# WAVESeeed.net
KiCad netlist of a schematic drawn in EAGLE
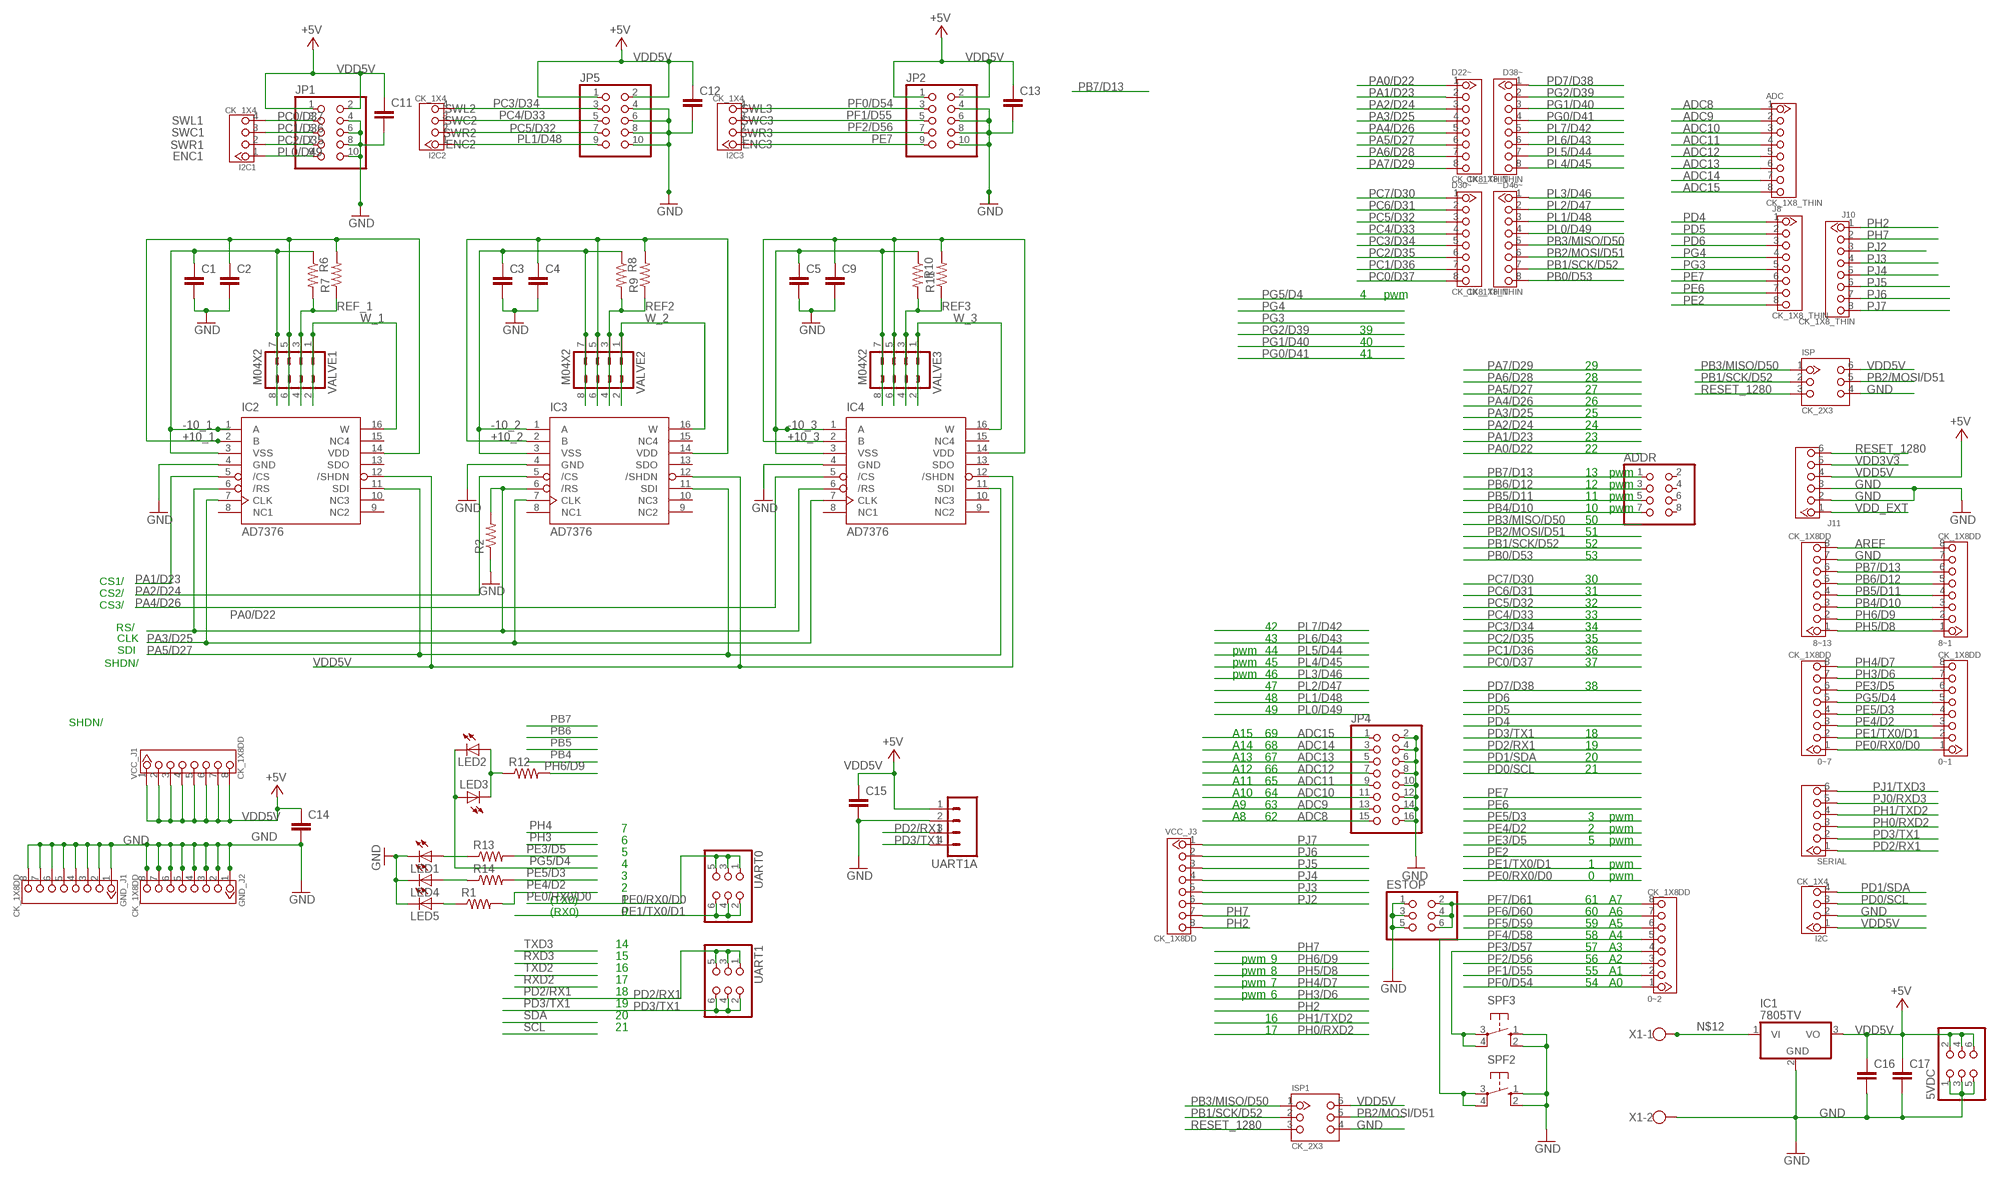
[diagram p0: schematic, sheet 1]

(export (version "E")
  (design (tool "Eeschema 10.0.6"))
  (components
    (comp (ref "0~1")
      (value "CK_1X8DD")
      (footprint "eagle-import:CK_1X8")
      (libsource (lib "eagle-import") (part "CK_1X8DD"))
    )
    (comp (ref "0~2")
      (value "CK_1X8DD")
      (footprint "eagle-import:CK_1X8")
      (libsource (lib "eagle-import") (part "CK_1X8DD"))
    )
    (comp (ref "0~7")
      (value "CK_1X8DD")
      (footprint "eagle-import:CK_1X8")
      (libsource (lib "eagle-import") (part "CK_1X8DD"))
    )
    (comp (ref "5VDC")
      (value "PINHD-2X3")
      (footprint "eagle-import:2X03")
      (libsource (lib "eagle-import") (part "PINHD-2X3"))
    )
    (comp (ref "8~1")
      (value "CK_1X8DD")
      (footprint "eagle-import:CK_1X8")
      (libsource (lib "eagle-import") (part "CK_1X8DD"))
    )
    (comp (ref "8~13")
      (value "CK_1X8DD")
      (footprint "eagle-import:CK_1X8")
      (libsource (lib "eagle-import") (part "CK_1X8DD"))
    )
    (comp (ref "ADC")
      (value "CK_1X8_THIN")
      (footprint "eagle-import:CK_1X8_THIN")
      (libsource (lib "eagle-import") (part "CK_1X8_THIN"))
    )
    (comp (ref "ADDR")
      (value "PINHD-2X4")
      (footprint "eagle-import:2X04")
      (libsource (lib "eagle-import") (part "PINHD-2X4"))
    )
    (comp (ref "C1")
      (value "C-EUC1206")
      (footprint "eagle-import:C1206")
      (libsource (lib "eagle-import") (part "C-EUC1206"))
    )
    (comp (ref "C2")
      (value "C-EUC1206")
      (footprint "eagle-import:C1206")
      (libsource (lib "eagle-import") (part "C-EUC1206"))
    )
    (comp (ref "C3")
      (value "C-EUC1206")
      (footprint "eagle-import:C1206")
      (libsource (lib "eagle-import") (part "C-EUC1206"))
    )
    (comp (ref "C4")
      (value "C-EUC1206")
      (footprint "eagle-import:C1206")
      (libsource (lib "eagle-import") (part "C-EUC1206"))
    )
    (comp (ref "C5")
      (value "C-EUC1206")
      (footprint "eagle-import:C1206")
      (libsource (lib "eagle-import") (part "C-EUC1206"))
    )
    (comp (ref "C9")
      (value "C-EUC1206")
      (footprint "eagle-import:C1206")
      (libsource (lib "eagle-import") (part "C-EUC1206"))
    )
    (comp (ref "C11")
      (value "C-EUC1206")
      (footprint "eagle-import:C1206")
      (libsource (lib "eagle-import") (part "C-EUC1206"))
    )
    (comp (ref "C12")
      (value "C-EUC1206K")
      (footprint "eagle-import:C1206K")
      (libsource (lib "eagle-import") (part "C-EUC1206K"))
    )
    (comp (ref "C13")
      (value "C-EUC1206K")
      (footprint "eagle-import:C1206K")
      (libsource (lib "eagle-import") (part "C-EUC1206K"))
    )
    (comp (ref "C14")
      (value "C-EUC1206K")
      (footprint "eagle-import:C1206K")
      (libsource (lib "eagle-import") (part "C-EUC1206K"))
    )
    (comp (ref "C15")
      (value "C-EUC1206")
      (footprint "eagle-import:C1206")
      (libsource (lib "eagle-import") (part "C-EUC1206"))
    )
    (comp (ref "C16")
      (value "C-EUC1206")
      (footprint "eagle-import:C1206")
      (libsource (lib "eagle-import") (part "C-EUC1206"))
    )
    (comp (ref "C17")
      (value "C-EUC1206K")
      (footprint "eagle-import:C1206K")
      (libsource (lib "eagle-import") (part "C-EUC1206K"))
    )
    (comp (ref "D22~")
      (value "CK_1X8_THIN")
      (footprint "eagle-import:CK_1X8_THIN")
      (libsource (lib "eagle-import") (part "CK_1X8_THIN"))
    )
    (comp (ref "D30~")
      (value "CK_1X8_THIN")
      (footprint "eagle-import:CK_1X8_THIN")
      (libsource (lib "eagle-import") (part "CK_1X8_THIN"))
    )
    (comp (ref "D38~")
      (value "CK_1X8_THIN")
      (footprint "eagle-import:CK_1X8_THIN")
      (libsource (lib "eagle-import") (part "CK_1X8_THIN"))
    )
    (comp (ref "D46~")
      (value "CK_1X8_THIN")
      (footprint "eagle-import:CK_1X8_THIN")
      (libsource (lib "eagle-import") (part "CK_1X8_THIN"))
    )
    (comp (ref "ESTOP")
      (value "PINHD-2X3")
      (footprint "eagle-import:2X03")
      (libsource (lib "eagle-import") (part "PINHD-2X3"))
    )
    (comp (ref "GND_J1")
      (value "CK_1X8DD")
      (footprint "eagle-import:CK_1X8")
      (libsource (lib "eagle-import") (part "CK_1X8DD"))
    )
    (comp (ref "GND_J2")
      (value "CK_1X8DD")
      (footprint "eagle-import:CK_1X8")
      (libsource (lib "eagle-import") (part "CK_1X8DD"))
    )
    (comp (ref "I2C")
      (value "CK_1X4")
      (footprint "eagle-import:CK_1X4")
      (libsource (lib "eagle-import") (part "CK_1X4_DD"))
    )
    (comp (ref "I2C1")
      (value "CK_1X4")
      (footprint "eagle-import:CK_1X4")
      (libsource (lib "eagle-import") (part "CK_1X4_DD"))
    )
    (comp (ref "I2C2")
      (value "CK_1X4")
      (footprint "eagle-import:CK_1X4")
      (libsource (lib "eagle-import") (part "CK_1X4_DD"))
    )
    (comp (ref "I2C3")
      (value "CK_1X4")
      (footprint "eagle-import:CK_1X4")
      (libsource (lib "eagle-import") (part "CK_1X4_DD"))
    )
    (comp (ref "IC1")
      (value "7805TV")
      (footprint "eagle-import:TO220V")
      (libsource (lib "eagle-import") (part "78TV05"))
    )
    (comp (ref "IC2")
      (value "AD7376")
      (footprint "eagle-import:SO-16W")
      (libsource (lib "eagle-import") (part "AD7376"))
    )
    (comp (ref "IC3")
      (value "AD7376")
      (footprint "eagle-import:SO-16W")
      (libsource (lib "eagle-import") (part "AD7376"))
    )
    (comp (ref "IC4")
      (value "AD7376")
      (footprint "eagle-import:SO-16W")
      (libsource (lib "eagle-import") (part "AD7376"))
    )
    (comp (ref "ISP")
      (value "CK_2X3")
      (footprint "eagle-import:CK_2X3_THIN")
      (libsource (lib "eagle-import") (part "CK_2X3_THIN"))
    )
    (comp (ref "ISP1")
      (value "CK_2X3")
      (footprint "eagle-import:CK_2X3_THIN")
      (libsource (lib "eagle-import") (part "CK_2X3_THIN"))
    )
    (comp (ref "J8")
      (value "CK_1X8_THIN")
      (footprint "eagle-import:CK_1X8_THIN")
      (libsource (lib "eagle-import") (part "CK_1X8_THIN"))
    )
    (comp (ref "J10")
      (value "CK_1X8_THIN")
      (footprint "eagle-import:CK_1X8_THIN")
      (libsource (lib "eagle-import") (part "CK_1X8_THIN"))
    )
    (comp (ref "J11")
      (value "CK_1X6")
      (footprint "eagle-import:CK_1X6")
      (libsource (lib "eagle-import") (part "CK_1X6"))
    )
    (comp (ref "JP1")
      (value "PINHD-2X5")
      (footprint "eagle-import:2X05")
      (libsource (lib "eagle-import") (part "PINHD-2X5"))
    )
    (comp (ref "JP2")
      (value "PINHD-2X5")
      (footprint "eagle-import:2X05")
      (libsource (lib "eagle-import") (part "PINHD-2X5"))
    )
    (comp (ref "JP4")
      (value "PINHD-2X8")
      (footprint "eagle-import:2X08")
      (libsource (lib "eagle-import") (part "PINHD-2X8"))
    )
    (comp (ref "JP5")
      (value "PINHD-2X5")
      (footprint "eagle-import:2X05")
      (libsource (lib "eagle-import") (part "PINHD-2X5"))
    )
    (comp (ref "LED1")
      (value "LEDCHIPLED_1206")
      (footprint "eagle-import:CHIPLED_1206")
      (libsource (lib "eagle-import") (part "LEDCHIPLED_1206"))
    )
    (comp (ref "LED2")
      (value "LEDCHIPLED_1206")
      (footprint "eagle-import:CHIPLED_1206")
      (libsource (lib "eagle-import") (part "LEDCHIPLED_1206"))
    )
    (comp (ref "LED3")
      (value "LEDCHIPLED_1206")
      (footprint "eagle-import:CHIPLED_1206")
      (libsource (lib "eagle-import") (part "LEDCHIPLED_1206"))
    )
    (comp (ref "LED4")
      (value "LEDCHIPLED_1206")
      (footprint "eagle-import:CHIPLED_1206")
      (libsource (lib "eagle-import") (part "LEDCHIPLED_1206"))
    )
    (comp (ref "LED5")
      (value "LEDCHIPLED_1206")
      (footprint "eagle-import:CHIPLED_1206")
      (libsource (lib "eagle-import") (part "LEDCHIPLED_1206"))
    )
    (comp (ref "R1")
      (value "R-US_R1206")
      (footprint "eagle-import:R1206")
      (libsource (lib "eagle-import") (part "R-US_R1206"))
    )
    (comp (ref "R2")
      (value "R-US_R1206")
      (footprint "eagle-import:R1206")
      (libsource (lib "eagle-import") (part "R-US_R1206"))
    )
    (comp (ref "R6")
      (value "R-US_M1206")
      (footprint "eagle-import:M1206")
      (libsource (lib "eagle-import") (part "R-US_M1206"))
    )
    (comp (ref "R7")
      (value "R-US_M1206")
      (footprint "eagle-import:M1206")
      (libsource (lib "eagle-import") (part "R-US_M1206"))
    )
    (comp (ref "R8")
      (value "R-US_M1206")
      (footprint "eagle-import:M1206")
      (libsource (lib "eagle-import") (part "R-US_M1206"))
    )
    (comp (ref "R9")
      (value "R-US_M1206")
      (footprint "eagle-import:M1206")
      (libsource (lib "eagle-import") (part "R-US_M1206"))
    )
    (comp (ref "R10")
      (value "R-US_M1206")
      (footprint "eagle-import:M1206")
      (libsource (lib "eagle-import") (part "R-US_M1206"))
    )
    (comp (ref "R11")
      (value "R-US_M1206")
      (footprint "eagle-import:M1206")
      (libsource (lib "eagle-import") (part "R-US_M1206"))
    )
    (comp (ref "R12")
      (value "R-US_R1206")
      (footprint "eagle-import:R1206")
      (libsource (lib "eagle-import") (part "R-US_R1206"))
    )
    (comp (ref "R13")
      (value "R-US_R1206")
      (footprint "eagle-import:R1206")
      (libsource (lib "eagle-import") (part "R-US_R1206"))
    )
    (comp (ref "R14")
      (value "R-US_R1206")
      (footprint "eagle-import:R1206")
      (libsource (lib "eagle-import") (part "R-US_R1206"))
    )
    (comp (ref "SERIAL")
      (value "CK_1X6")
      (footprint "eagle-import:CK_1X6")
      (libsource (lib "eagle-import") (part "CK_1X6"))
    )
    (comp (ref "SPF2")
      (value "10-XX")
      (footprint "eagle-import:B3F-10XX")
      (fields (field (name "MPN") "B3F-1000"))
      (libsource (lib "eagle-import") (part "10-XX"))
    )
    (comp (ref "SPF3")
      (value "10-XX")
      (footprint "eagle-import:B3F-10XX")
      (fields (field (name "MPN") "B3F-1000"))
      (libsource (lib "eagle-import") (part "10-XX"))
    )
    (comp (ref "UART0")
      (value "PINHD-2X3")
      (footprint "eagle-import:2X03")
      (libsource (lib "eagle-import") (part "PINHD-2X3"))
    )
    (comp (ref "UART1")
      (value "PINHD-2X3")
      (footprint "eagle-import:2X03")
      (libsource (lib "eagle-import") (part "PINHD-2X3"))
    )
    (comp (ref "UART1A")
      (value "M04PTH")
      (footprint "eagle-import:1X04")
      (libsource (lib "eagle-import") (part "M04PTH"))
    )
    (comp (ref "VALVE1")
      (value "M04X2")
      (footprint "eagle-import:2X4")
      (libsource (lib "eagle-import") (part "M04X2"))
    )
    (comp (ref "VALVE2")
      (value "M04X2")
      (footprint "eagle-import:2X4")
      (libsource (lib "eagle-import") (part "M04X2"))
    )
    (comp (ref "VALVE3")
      (value "M04X2")
      (footprint "eagle-import:2X4")
      (libsource (lib "eagle-import") (part "M04X2"))
    )
    (comp (ref "VCC_J1")
      (value "CK_1X8DD")
      (footprint "eagle-import:CK_1X8")
      (libsource (lib "eagle-import") (part "CK_1X8DD"))
    )
    (comp (ref "VCC_J3")
      (value "CK_1X8DD")
      (footprint "eagle-import:CK_1X8")
      (libsource (lib "eagle-import") (part "CK_1X8DD"))
    )
    (comp (ref "X1")
      (value "W237-102")
      (footprint "eagle-import:W237-102")
      (fields (field (name "MPN") "237-102"))
      (libsource (lib "eagle-import") (part "W237-102"))
    )
  )
  (nets
    (net (code "1") (name "+5V") (class "Default")
      (node (ref "5VDC") (pin "2") (pinfunction "2_2") (pintype "passive"))
      (node (ref "5VDC") (pin "4") (pinfunction "4_4") (pintype "passive"))
      (node (ref "5VDC") (pin "6") (pinfunction "6_6") (pintype "passive"))
      (node (ref "C11") (pin "1") (pinfunction "1_1") (pintype "passive"))
      (node (ref "C12") (pin "1") (pinfunction "1_1") (pintype "passive"))
      (node (ref "C13") (pin "1") (pinfunction "1_1") (pintype "passive"))
      (node (ref "C14") (pin "1") (pinfunction "1_1") (pintype "passive"))
      (node (ref "C15") (pin "1") (pinfunction "1_1") (pintype "passive"))
      (node (ref "C16") (pin "1") (pinfunction "1_1") (pintype "passive"))
      (node (ref "C17") (pin "1") (pinfunction "1_1") (pintype "passive"))
      (node (ref "I2C") (pin "1") (pinfunction "P$1_1") (pintype "bidirectional"))
      (node (ref "IC1") (pin "3") (pinfunction "VO_3") (pintype "passive"))
      (node (ref "IC2") (pin "12") (pinfunction "/SHDN_12") (pintype "input"))
      (node (ref "IC3") (pin "12") (pinfunction "/SHDN_12") (pintype "input"))
      (node (ref "IC4") (pin "12") (pinfunction "/SHDN_12") (pintype "input"))
      (node (ref "ISP") (pin "6") (pinfunction "P$6_6") (pintype "bidirectional"))
      (node (ref "ISP1") (pin "6") (pinfunction "P$6_6") (pintype "bidirectional"))
      (node (ref "J11") (pin "4") (pinfunction "4_4") (pintype "bidirectional"))
      (node (ref "JP1") (pin "1") (pinfunction "1_1") (pintype "passive"))
      (node (ref "JP1") (pin "2") (pinfunction "2_2") (pintype "passive"))
      (node (ref "JP2") (pin "1") (pinfunction "1_1") (pintype "passive"))
      (node (ref "JP2") (pin "2") (pinfunction "2_2") (pintype "passive"))
      (node (ref "JP5") (pin "1") (pinfunction "1_1") (pintype "passive"))
      (node (ref "JP5") (pin "2") (pinfunction "2_2") (pintype "passive"))
      (node (ref "UART1A") (pin "1") (pinfunction "1_1") (pintype "passive"))
      (node (ref "VCC_J1") (pin "1") (pinfunction "P$1_1") (pintype "bidirectional"))
      (node (ref "VCC_J1") (pin "2") (pinfunction "P$2_2") (pintype "bidirectional"))
      (node (ref "VCC_J1") (pin "3") (pinfunction "P$3_3") (pintype "bidirectional"))
      (node (ref "VCC_J1") (pin "4") (pinfunction "P$4_4") (pintype "bidirectional"))
      (node (ref "VCC_J1") (pin "5") (pinfunction "P$5_5") (pintype "bidirectional"))
      (node (ref "VCC_J1") (pin "6") (pinfunction "P$6_6") (pintype "bidirectional"))
      (node (ref "VCC_J1") (pin "7") (pinfunction "P$7_7") (pintype "bidirectional"))
      (node (ref "VCC_J1") (pin "8") (pinfunction "P$8_8") (pintype "bidirectional"))
    )
    (net (code "2") (name "/+10_1") (class "Default")
      (node (ref "C2") (pin "1") (pinfunction "1_1") (pintype "passive"))
      (node (ref "IC2") (pin "14") (pinfunction "VDD_14") (pintype "power_in"))
      (node (ref "IC2") (pin "2") (pinfunction "B_2") (pintype "bidirectional"))
      (node (ref "R7") (pin "2") (pinfunction "2_2") (pintype "passive"))
      (node (ref "VALVE1") (pin "5") (pinfunction "5_5") (pintype "passive"))
      (node (ref "VALVE1") (pin "6") (pinfunction "6_6") (pintype "passive"))
    )
    (net (code "3") (name "/+10_2") (class "Default")
      (node (ref "C4") (pin "1") (pinfunction "1_1") (pintype "passive"))
      (node (ref "IC3") (pin "14") (pinfunction "VDD_14") (pintype "power_in"))
      (node (ref "IC3") (pin "2") (pinfunction "B_2") (pintype "bidirectional"))
      (node (ref "R9") (pin "2") (pinfunction "2_2") (pintype "passive"))
      (node (ref "VALVE2") (pin "5") (pinfunction "5_5") (pintype "passive"))
      (node (ref "VALVE2") (pin "6") (pinfunction "6_6") (pintype "passive"))
    )
    (net (code "4") (name "/+10_3") (class "Default")
      (node (ref "C9") (pin "1") (pinfunction "1_1") (pintype "passive"))
      (node (ref "IC4") (pin "14") (pinfunction "VDD_14") (pintype "power_in"))
      (node (ref "IC4") (pin "2") (pinfunction "B_2") (pintype "bidirectional"))
      (node (ref "R11") (pin "2") (pinfunction "2_2") (pintype "passive"))
      (node (ref "VALVE3") (pin "5") (pinfunction "5_5") (pintype "passive"))
      (node (ref "VALVE3") (pin "6") (pinfunction "6_6") (pintype "passive"))
    )
    (net (code "5") (name "/-10_1") (class "Default")
      (node (ref "C1") (pin "1") (pinfunction "1_1") (pintype "passive"))
      (node (ref "IC2") (pin "1") (pinfunction "A_1") (pintype "bidirectional"))
      (node (ref "IC2") (pin "3") (pinfunction "VSS_3") (pintype "power_in"))
      (node (ref "R6") (pin "1") (pinfunction "1_1") (pintype "passive"))
      (node (ref "VALVE1") (pin "7") (pinfunction "7_7") (pintype "passive"))
      (node (ref "VALVE1") (pin "8") (pinfunction "8_8") (pintype "passive"))
    )
    (net (code "6") (name "/-10_2") (class "Default")
      (node (ref "C3") (pin "1") (pinfunction "1_1") (pintype "passive"))
      (node (ref "IC3") (pin "1") (pinfunction "A_1") (pintype "bidirectional"))
      (node (ref "IC3") (pin "3") (pinfunction "VSS_3") (pintype "power_in"))
      (node (ref "R8") (pin "1") (pinfunction "1_1") (pintype "passive"))
      (node (ref "VALVE2") (pin "7") (pinfunction "7_7") (pintype "passive"))
      (node (ref "VALVE2") (pin "8") (pinfunction "8_8") (pintype "passive"))
    )
    (net (code "7") (name "/-10_3") (class "Default")
      (node (ref "C5") (pin "1") (pinfunction "1_1") (pintype "passive"))
      (node (ref "IC4") (pin "1") (pinfunction "A_1") (pintype "bidirectional"))
      (node (ref "IC4") (pin "3") (pinfunction "VSS_3") (pintype "power_in"))
      (node (ref "R10") (pin "1") (pinfunction "1_1") (pintype "passive"))
      (node (ref "VALVE3") (pin "7") (pinfunction "7_7") (pintype "passive"))
      (node (ref "VALVE3") (pin "8") (pinfunction "8_8") (pintype "passive"))
    )
    (net (code "8") (name "/ADC8") (class "Default")
      (node (ref "ADC") (pin "1") (pinfunction "P$1_1") (pintype "bidirectional"))
      (node (ref "JP4") (pin "15") (pinfunction "15_15") (pintype "passive"))
    )
    (net (code "9") (name "/ADC9") (class "Default")
      (node (ref "ADC") (pin "2") (pinfunction "P$2_2") (pintype "bidirectional"))
      (node (ref "JP4") (pin "13") (pinfunction "13_13") (pintype "passive"))
    )
    (net (code "10") (name "/ADC10") (class "Default")
      (node (ref "ADC") (pin "3") (pinfunction "P$3_3") (pintype "bidirectional"))
      (node (ref "JP4") (pin "11") (pinfunction "11_11") (pintype "passive"))
    )
    (net (code "11") (name "/ADC11") (class "Default")
      (node (ref "ADC") (pin "4") (pinfunction "P$4_4") (pintype "bidirectional"))
      (node (ref "JP4") (pin "9") (pinfunction "9_9") (pintype "passive"))
    )
    (net (code "12") (name "/ADC12") (class "Default")
      (node (ref "ADC") (pin "5") (pinfunction "P$5_5") (pintype "bidirectional"))
      (node (ref "JP4") (pin "7") (pinfunction "7_7") (pintype "passive"))
    )
    (net (code "13") (name "/ADC13") (class "Default")
      (node (ref "ADC") (pin "6") (pinfunction "P$6_6") (pintype "bidirectional"))
      (node (ref "JP4") (pin "5") (pinfunction "5_5") (pintype "passive"))
    )
    (net (code "14") (name "/ADC14") (class "Default")
      (node (ref "ADC") (pin "7") (pinfunction "P$7_7") (pintype "bidirectional"))
      (node (ref "JP4") (pin "3") (pinfunction "3_3") (pintype "passive"))
    )
    (net (code "15") (name "/ADC15") (class "Default")
      (node (ref "ADC") (pin "8") (pinfunction "P$8_8") (pintype "bidirectional"))
      (node (ref "JP4") (pin "1") (pinfunction "1_1") (pintype "passive"))
    )
    (net (code "16") (name "/AREF") (class "Default")
      (node (ref "8~1") (pin "8") (pinfunction "P$8_8") (pintype "bidirectional"))
      (node (ref "8~13") (pin "8") (pinfunction "P$8_8") (pintype "bidirectional"))
    )
    (net (code "17") (name "/N$12") (class "Default")
      (node (ref "IC1") (pin "1") (pinfunction "VI_1") (pintype "input"))
      (node (ref "X1") (pin "1") (pinfunction "KL_1") (pintype "passive"))
    )
    (net (code "18") (name "/PA0{slash}D22") (class "Default")
      (node (ref "D22~") (pin "1") (pinfunction "P$1_1") (pintype "bidirectional"))
      (node (ref "IC2") (pin "6") (pinfunction "/RS_6") (pintype "input"))
      (node (ref "IC3") (pin "6") (pinfunction "/RS_6") (pintype "input"))
      (node (ref "IC4") (pin "6") (pinfunction "/RS_6") (pintype "input"))
      (node (ref "R2") (pin "2") (pinfunction "2_2") (pintype "passive"))
    )
    (net (code "19") (name "/PA1{slash}D23") (class "Default")
      (node (ref "D22~") (pin "2") (pinfunction "P$2_2") (pintype "bidirectional"))
      (node (ref "IC2") (pin "5") (pinfunction "/CS_5") (pintype "input"))
    )
    (net (code "20") (name "/PA2{slash}D24") (class "Default")
      (node (ref "D22~") (pin "3") (pinfunction "P$3_3") (pintype "bidirectional"))
      (node (ref "IC3") (pin "5") (pinfunction "/CS_5") (pintype "input"))
    )
    (net (code "21") (name "/PA3{slash}D25") (class "Default")
      (node (ref "D22~") (pin "4") (pinfunction "P$4_4") (pintype "bidirectional"))
      (node (ref "IC2") (pin "7") (pinfunction "CLK_7") (pintype "input"))
      (node (ref "IC3") (pin "7") (pinfunction "CLK_7") (pintype "input"))
      (node (ref "IC4") (pin "7") (pinfunction "CLK_7") (pintype "input"))
    )
    (net (code "22") (name "/PA4{slash}D26") (class "Default")
      (node (ref "D22~") (pin "5") (pinfunction "P$5_5") (pintype "bidirectional"))
      (node (ref "IC4") (pin "5") (pinfunction "/CS_5") (pintype "input"))
    )
    (net (code "23") (name "/PA5{slash}D27") (class "Default")
      (node (ref "D22~") (pin "6") (pinfunction "P$6_6") (pintype "bidirectional"))
      (node (ref "IC2") (pin "11") (pinfunction "SDI_11") (pintype "input"))
      (node (ref "IC3") (pin "11") (pinfunction "SDI_11") (pintype "input"))
      (node (ref "IC4") (pin "11") (pinfunction "SDI_11") (pintype "input"))
    )
    (net (code "24") (name "/PA6{slash}D28") (class "Default")
      (node (ref "D22~") (pin "7") (pinfunction "P$7_7") (pintype "bidirectional"))
    )
    (net (code "25") (name "/PA7{slash}D29") (class "Default")
      (node (ref "D22~") (pin "8") (pinfunction "P$8_8") (pintype "bidirectional"))
    )
    (net (code "26") (name "/PB0{slash}D53") (class "Default")
      (node (ref "D46~") (pin "8") (pinfunction "P$8_8") (pintype "bidirectional"))
    )
    (net (code "27") (name "/PB1{slash}SCK{slash}D52") (class "Default")
      (node (ref "D46~") (pin "7") (pinfunction "P$7_7") (pintype "bidirectional"))
      (node (ref "ISP") (pin "2") (pinfunction "P$2_2") (pintype "bidirectional"))
      (node (ref "ISP1") (pin "2") (pinfunction "P$2_2") (pintype "bidirectional"))
    )
    (net (code "28") (name "/PB2{slash}MOSI{slash}D51") (class "Default")
      (node (ref "D46~") (pin "6") (pinfunction "P$6_6") (pintype "bidirectional"))
      (node (ref "ISP") (pin "5") (pinfunction "P$5_5") (pintype "bidirectional"))
      (node (ref "ISP1") (pin "5") (pinfunction "P$5_5") (pintype "bidirectional"))
    )
    (net (code "29") (name "/PB3{slash}MISO{slash}D50") (class "Default")
      (node (ref "D46~") (pin "5") (pinfunction "P$5_5") (pintype "bidirectional"))
      (node (ref "ISP") (pin "1") (pinfunction "P$1_1") (pintype "bidirectional"))
      (node (ref "ISP1") (pin "1") (pinfunction "P$1_1") (pintype "bidirectional"))
    )
    (net (code "31") (name "/PB4{slash}D10") (class "Default")
      (node (ref "8~1") (pin "3") (pinfunction "P$3_3") (pintype "bidirectional"))
      (node (ref "8~13") (pin "3") (pinfunction "P$3_3") (pintype "bidirectional"))
      (node (ref "ADDR") (pin "7") (pinfunction "7_7") (pintype "passive"))
    )
    (net (code "33") (name "/PB5{slash}D11") (class "Default")
      (node (ref "8~1") (pin "4") (pinfunction "P$4_4") (pintype "bidirectional"))
      (node (ref "8~13") (pin "4") (pinfunction "P$4_4") (pintype "bidirectional"))
      (node (ref "ADDR") (pin "5") (pinfunction "5_5") (pintype "passive"))
    )
    (net (code "35") (name "/PB6{slash}D12") (class "Default")
      (node (ref "8~1") (pin "5") (pinfunction "P$5_5") (pintype "bidirectional"))
      (node (ref "8~13") (pin "5") (pinfunction "P$5_5") (pintype "bidirectional"))
      (node (ref "ADDR") (pin "3") (pinfunction "3_3") (pintype "passive"))
    )
    (net (code "37") (name "/PB7{slash}D13") (class "Default")
      (node (ref "8~1") (pin "6") (pinfunction "P$6_6") (pintype "bidirectional"))
      (node (ref "8~13") (pin "6") (pinfunction "P$6_6") (pintype "bidirectional"))
      (node (ref "ADDR") (pin "1") (pinfunction "1_1") (pintype "passive"))
    )
    (net (code "38") (name "/PC0{slash}D37") (class "Default")
      (node (ref "D30~") (pin "8") (pinfunction "P$8_8") (pintype "bidirectional"))
      (node (ref "I2C1") (pin "4") (pinfunction "P$4_4") (pintype "bidirectional"))
      (node (ref "JP1") (pin "3") (pinfunction "3_3") (pintype "passive"))
    )
    (net (code "39") (name "/PC1{slash}D36") (class "Default")
      (node (ref "D30~") (pin "7") (pinfunction "P$7_7") (pintype "bidirectional"))
      (node (ref "I2C1") (pin "3") (pinfunction "P$3_3") (pintype "bidirectional"))
      (node (ref "JP1") (pin "5") (pinfunction "5_5") (pintype "passive"))
    )
    (net (code "40") (name "/PC2{slash}D35") (class "Default")
      (node (ref "D30~") (pin "6") (pinfunction "P$6_6") (pintype "bidirectional"))
      (node (ref "I2C1") (pin "2") (pinfunction "P$2_2") (pintype "bidirectional"))
      (node (ref "JP1") (pin "7") (pinfunction "7_7") (pintype "passive"))
    )
    (net (code "41") (name "/PC3{slash}D34") (class "Default")
      (node (ref "D30~") (pin "5") (pinfunction "P$5_5") (pintype "bidirectional"))
      (node (ref "I2C2") (pin "4") (pinfunction "P$4_4") (pintype "bidirectional"))
      (node (ref "JP5") (pin "3") (pinfunction "3_3") (pintype "passive"))
    )
    (net (code "42") (name "/PC4{slash}D33") (class "Default")
      (node (ref "D30~") (pin "4") (pinfunction "P$4_4") (pintype "bidirectional"))
      (node (ref "I2C2") (pin "3") (pinfunction "P$3_3") (pintype "bidirectional"))
      (node (ref "JP5") (pin "5") (pinfunction "5_5") (pintype "passive"))
    )
    (net (code "43") (name "/PC5{slash}D32") (class "Default")
      (node (ref "D30~") (pin "3") (pinfunction "P$3_3") (pintype "bidirectional"))
      (node (ref "I2C2") (pin "2") (pinfunction "P$2_2") (pintype "bidirectional"))
      (node (ref "JP5") (pin "7") (pinfunction "7_7") (pintype "passive"))
    )
    (net (code "44") (name "/PC6{slash}D31") (class "Default")
      (node (ref "D30~") (pin "2") (pinfunction "P$2_2") (pintype "bidirectional"))
    )
    (net (code "45") (name "/PC7{slash}D30") (class "Default")
      (node (ref "D30~") (pin "1") (pinfunction "P$1_1") (pintype "bidirectional"))
    )
    (net (code "46") (name "/PD0{slash}SCL") (class "Default")
      (node (ref "I2C") (pin "3") (pinfunction "P$3_3") (pintype "bidirectional"))
    )
    (net (code "47") (name "/PD1{slash}SDA") (class "Default")
      (node (ref "I2C") (pin "4") (pinfunction "P$4_4") (pintype "bidirectional"))
    )
    (net (code "48") (name "/PD2{slash}RX1") (class "Default")
      (node (ref "SERIAL") (pin "1") (pinfunction "1_1") (pintype "bidirectional"))
      (node (ref "UART1") (pin "1") (pinfunction "1_1") (pintype "passive"))
      (node (ref "UART1") (pin "3") (pinfunction "3_3") (pintype "passive"))
      (node (ref "UART1") (pin "5") (pinfunction "5_5") (pintype "passive"))
      (node (ref "UART1A") (pin "3") (pinfunction "3_3") (pintype "passive"))
    )
    (net (code "49") (name "/PD3{slash}TX1") (class "Default")
      (node (ref "SERIAL") (pin "2") (pinfunction "2_2") (pintype "bidirectional"))
      (node (ref "UART1") (pin "2") (pinfunction "2_2") (pintype "passive"))
      (node (ref "UART1") (pin "4") (pinfunction "4_4") (pintype "passive"))
      (node (ref "UART1") (pin "6") (pinfunction "6_6") (pintype "passive"))
      (node (ref "UART1A") (pin "4") (pinfunction "4_4") (pintype "passive"))
    )
    (net (code "50") (name "/PD4") (class "Default")
      (node (ref "J8") (pin "1") (pinfunction "P$1_1") (pintype "bidirectional"))
    )
    (net (code "51") (name "/PD5") (class "Default")
      (node (ref "J8") (pin "2") (pinfunction "P$2_2") (pintype "bidirectional"))
    )
    (net (code "52") (name "/PD6") (class "Default")
      (node (ref "J8") (pin "3") (pinfunction "P$3_3") (pintype "bidirectional"))
    )
    (net (code "53") (name "/PD7{slash}D38") (class "Default")
      (node (ref "D38~") (pin "1") (pinfunction "P$1_1") (pintype "bidirectional"))
    )
    (net (code "54") (name "/PE0{slash}RX0{slash}D0") (class "Default")
      (node (ref "0~1") (pin "1") (pinfunction "P$1_1") (pintype "bidirectional"))
      (node (ref "0~7") (pin "1") (pinfunction "P$1_1") (pintype "bidirectional"))
      (node (ref "UART0") (pin "1") (pinfunction "1_1") (pintype "passive"))
      (node (ref "UART0") (pin "3") (pinfunction "3_3") (pintype "passive"))
      (node (ref "UART0") (pin "5") (pinfunction "5_5") (pintype "passive"))
    )
    (net (code "55") (name "/PE1{slash}TX0{slash}D1") (class "Default")
      (node (ref "0~1") (pin "2") (pinfunction "P$2_2") (pintype "bidirectional"))
      (node (ref "0~7") (pin "2") (pinfunction "P$2_2") (pintype "bidirectional"))
      (node (ref "UART0") (pin "2") (pinfunction "2_2") (pintype "passive"))
      (node (ref "UART0") (pin "4") (pinfunction "4_4") (pintype "passive"))
      (node (ref "UART0") (pin "6") (pinfunction "6_6") (pintype "passive"))
    )
    (net (code "56") (name "/PE2") (class "Default")
      (node (ref "J8") (pin "8") (pinfunction "P$8_8") (pintype "bidirectional"))
    )
    (net (code "57") (name "/PE3{slash}D5") (class "Default")
      (node (ref "0~1") (pin "6") (pinfunction "P$6_6") (pintype "bidirectional"))
      (node (ref "0~7") (pin "6") (pinfunction "P$6_6") (pintype "bidirectional"))
      (node (ref "R13") (pin "2") (pinfunction "2_2") (pintype "passive"))
    )
    (net (code "58") (name "/PE4{slash}D2") (class "Default")
      (node (ref "0~1") (pin "3") (pinfunction "P$3_3") (pintype "bidirectional"))
      (node (ref "0~7") (pin "3") (pinfunction "P$3_3") (pintype "bidirectional"))
      (node (ref "R1") (pin "2") (pinfunction "2_2") (pintype "passive"))
    )
    (net (code "59") (name "/PE5{slash}D3") (class "Default")
      (node (ref "0~1") (pin "4") (pinfunction "P$4_4") (pintype "bidirectional"))
      (node (ref "0~7") (pin "4") (pinfunction "P$4_4") (pintype "bidirectional"))
      (node (ref "R14") (pin "2") (pinfunction "2_2") (pintype "passive"))
    )
    (net (code "60") (name "/PE6") (class "Default")
      (node (ref "J8") (pin "7") (pinfunction "P$7_7") (pintype "bidirectional"))
    )
    (net (code "61") (name "/PE7") (class "Default")
      (node (ref "I2C3") (pin "1") (pinfunction "P$1_1") (pintype "bidirectional"))
      (node (ref "J8") (pin "6") (pinfunction "P$6_6") (pintype "bidirectional"))
      (node (ref "JP2") (pin "9") (pinfunction "9_9") (pintype "passive"))
    )
    (net (code "62") (name "/PF0{slash}D54") (class "Default")
      (node (ref "0~2") (pin "1") (pinfunction "P$1_1") (pintype "bidirectional"))
      (node (ref "I2C3") (pin "4") (pinfunction "P$4_4") (pintype "bidirectional"))
      (node (ref "JP2") (pin "3") (pinfunction "3_3") (pintype "passive"))
    )
    (net (code "63") (name "/PF1{slash}D55") (class "Default")
      (node (ref "0~2") (pin "2") (pinfunction "P$2_2") (pintype "bidirectional"))
      (node (ref "I2C3") (pin "3") (pinfunction "P$3_3") (pintype "bidirectional"))
      (node (ref "JP2") (pin "5") (pinfunction "5_5") (pintype "passive"))
    )
    (net (code "64") (name "/PF2{slash}D56") (class "Default")
      (node (ref "0~2") (pin "3") (pinfunction "P$3_3") (pintype "bidirectional"))
      (node (ref "I2C3") (pin "2") (pinfunction "P$2_2") (pintype "bidirectional"))
      (node (ref "JP2") (pin "7") (pinfunction "7_7") (pintype "passive"))
    )
    (net (code "65") (name "/PF3{slash}D57") (class "Default")
      (node (ref "0~2") (pin "4") (pinfunction "P$4_4") (pintype "bidirectional"))
      (node (ref "SPF3") (pin "3") (pinfunction "P_3") (pintype "passive"))
      (node (ref "SPF3") (pin "4") (pinfunction "P1_4") (pintype "passive"))
    )
    (net (code "66") (name "/PF4{slash}D58") (class "Default")
      (node (ref "0~2") (pin "5") (pinfunction "P$5_5") (pintype "bidirectional"))
      (node (ref "SPF2") (pin "3") (pinfunction "P_3") (pintype "passive"))
      (node (ref "SPF2") (pin "4") (pinfunction "P1_4") (pintype "passive"))
    )
    (net (code "67") (name "/PF5{slash}D59") (class "Default")
      (node (ref "0~2") (pin "6") (pinfunction "P$6_6") (pintype "bidirectional"))
    )
    (net (code "68") (name "/PF6{slash}D60") (class "Default")
      (node (ref "0~2") (pin "7") (pinfunction "P$7_7") (pintype "bidirectional"))
    )
    (net (code "69") (name "/PF7{slash}D61") (class "Default")
      (node (ref "0~2") (pin "8") (pinfunction "P$8_8") (pintype "bidirectional"))
      (node (ref "ESTOP") (pin "2") (pinfunction "2_2") (pintype "passive"))
      (node (ref "ESTOP") (pin "4") (pinfunction "4_4") (pintype "passive"))
      (node (ref "ESTOP") (pin "6") (pinfunction "6_6") (pintype "passive"))
    )
    (net (code "70") (name "/PG0{slash}D41") (class "Default")
      (node (ref "D38~") (pin "4") (pinfunction "P$4_4") (pintype "bidirectional"))
    )
    (net (code "71") (name "/PG1{slash}D40") (class "Default")
      (node (ref "D38~") (pin "3") (pinfunction "P$3_3") (pintype "bidirectional"))
    )
    (net (code "72") (name "/PG2{slash}D39") (class "Default")
      (node (ref "D38~") (pin "2") (pinfunction "P$2_2") (pintype "bidirectional"))
    )
    (net (code "73") (name "/PG3") (class "Default")
      (node (ref "J8") (pin "5") (pinfunction "P$5_5") (pintype "bidirectional"))
    )
    (net (code "74") (name "/PG4") (class "Default")
      (node (ref "J8") (pin "4") (pinfunction "P$4_4") (pintype "bidirectional"))
    )
    (net (code "75") (name "/PG5{slash}D4") (class "Default")
      (node (ref "0~1") (pin "5") (pinfunction "P$5_5") (pintype "bidirectional"))
      (node (ref "0~7") (pin "5") (pinfunction "P$5_5") (pintype "bidirectional"))
      (node (ref "LED2") (pin "C") (pinfunction "C_C") (pintype "passive"))
      (node (ref "LED3") (pin "A") (pinfunction "A_A") (pintype "passive"))
    )
    (net (code "76") (name "/PH0{slash}RXD2") (class "Default")
      (node (ref "SERIAL") (pin "3") (pinfunction "3_3") (pintype "bidirectional"))
    )
    (net (code "77") (name "/PH1{slash}TXD2") (class "Default")
      (node (ref "SERIAL") (pin "4") (pinfunction "4_4") (pintype "bidirectional"))
    )
    (net (code "78") (name "/PH2") (class "Default")
      (node (ref "J10") (pin "1") (pinfunction "P$1_1") (pintype "bidirectional"))
      (node (ref "VCC_J3") (pin "8") (pinfunction "P$8_8") (pintype "bidirectional"))
    )
    (net (code "80") (name "/PH3{slash}D6") (class "Default")
      (node (ref "0~1") (pin "7") (pinfunction "P$7_7") (pintype "bidirectional"))
      (node (ref "0~7") (pin "7") (pinfunction "P$7_7") (pintype "bidirectional"))
    )
    (net (code "82") (name "/PH4{slash}D7") (class "Default")
      (node (ref "0~1") (pin "8") (pinfunction "P$8_8") (pintype "bidirectional"))
      (node (ref "0~7") (pin "8") (pinfunction "P$8_8") (pintype "bidirectional"))
    )
    (net (code "83") (name "/PH5{slash}D8") (class "Default")
      (node (ref "8~1") (pin "1") (pinfunction "P$1_1") (pintype "bidirectional"))
      (node (ref "8~13") (pin "1") (pinfunction "P$1_1") (pintype "bidirectional"))
    )
    (net (code "84") (name "/PH6{slash}D9") (class "Default")
      (node (ref "8~1") (pin "2") (pinfunction "P$2_2") (pintype "bidirectional"))
      (node (ref "8~13") (pin "2") (pinfunction "P$2_2") (pintype "bidirectional"))
      (node (ref "R12") (pin "2") (pinfunction "2_2") (pintype "passive"))
    )
    (net (code "85") (name "/PH7") (class "Default")
      (node (ref "J10") (pin "2") (pinfunction "P$2_2") (pintype "bidirectional"))
      (node (ref "VCC_J3") (pin "7") (pinfunction "P$7_7") (pintype "bidirectional"))
    )
    (net (code "86") (name "/PJ0{slash}RXD3") (class "Default")
      (node (ref "SERIAL") (pin "5") (pinfunction "5_5") (pintype "bidirectional"))
    )
    (net (code "87") (name "/PJ1{slash}TXD3") (class "Default")
      (node (ref "SERIAL") (pin "6") (pinfunction "6_6") (pintype "bidirectional"))
    )
    (net (code "88") (name "/PJ2") (class "Default")
      (node (ref "J10") (pin "3") (pinfunction "P$3_3") (pintype "bidirectional"))
      (node (ref "VCC_J3") (pin "6") (pinfunction "P$6_6") (pintype "bidirectional"))
    )
    (net (code "89") (name "/PJ3") (class "Default")
      (node (ref "J10") (pin "4") (pinfunction "P$4_4") (pintype "bidirectional"))
      (node (ref "VCC_J3") (pin "5") (pinfunction "P$5_5") (pintype "bidirectional"))
    )
    (net (code "90") (name "/PJ4") (class "Default")
      (node (ref "J10") (pin "5") (pinfunction "P$5_5") (pintype "bidirectional"))
      (node (ref "VCC_J3") (pin "4") (pinfunction "P$4_4") (pintype "bidirectional"))
    )
    (net (code "91") (name "/PJ5") (class "Default")
      (node (ref "J10") (pin "6") (pinfunction "P$6_6") (pintype "bidirectional"))
      (node (ref "VCC_J3") (pin "3") (pinfunction "P$3_3") (pintype "bidirectional"))
    )
    (net (code "92") (name "/PJ6") (class "Default")
      (node (ref "J10") (pin "7") (pinfunction "P$7_7") (pintype "bidirectional"))
      (node (ref "VCC_J3") (pin "2") (pinfunction "P$2_2") (pintype "bidirectional"))
    )
    (net (code "93") (name "/PJ7") (class "Default")
      (node (ref "J10") (pin "8") (pinfunction "P$8_8") (pintype "bidirectional"))
      (node (ref "VCC_J3") (pin "1") (pinfunction "P$1_1") (pintype "bidirectional"))
    )
    (net (code "94") (name "/PL0{slash}D49") (class "Default")
      (node (ref "D46~") (pin "4") (pinfunction "P$4_4") (pintype "bidirectional"))
      (node (ref "I2C1") (pin "1") (pinfunction "P$1_1") (pintype "bidirectional"))
      (node (ref "JP1") (pin "9") (pinfunction "9_9") (pintype "passive"))
    )
    (net (code "95") (name "/PL1{slash}D48") (class "Default")
      (node (ref "D46~") (pin "3") (pinfunction "P$3_3") (pintype "bidirectional"))
      (node (ref "I2C2") (pin "1") (pinfunction "P$1_1") (pintype "bidirectional"))
      (node (ref "JP5") (pin "9") (pinfunction "9_9") (pintype "passive"))
    )
    (net (code "96") (name "/PL2{slash}D47") (class "Default")
      (node (ref "D46~") (pin "2") (pinfunction "P$2_2") (pintype "bidirectional"))
    )
    (net (code "97") (name "/PL3{slash}D46") (class "Default")
      (node (ref "D46~") (pin "1") (pinfunction "P$1_1") (pintype "bidirectional"))
    )
    (net (code "98") (name "/PL4{slash}D45") (class "Default")
      (node (ref "D38~") (pin "8") (pinfunction "P$8_8") (pintype "bidirectional"))
    )
    (net (code "99") (name "/PL5{slash}D44") (class "Default")
      (node (ref "D38~") (pin "7") (pinfunction "P$7_7") (pintype "bidirectional"))
    )
    (net (code "100") (name "/PL6{slash}D43") (class "Default")
      (node (ref "D38~") (pin "6") (pinfunction "P$6_6") (pintype "bidirectional"))
    )
    (net (code "101") (name "/PL7{slash}D42") (class "Default")
      (node (ref "D38~") (pin "5") (pinfunction "P$5_5") (pintype "bidirectional"))
    )
    (net (code "102") (name "/REF2") (class "Default")
      (node (ref "R8") (pin "2") (pinfunction "2_2") (pintype "passive"))
      (node (ref "R9") (pin "1") (pinfunction "1_1") (pintype "passive"))
      (node (ref "VALVE2") (pin "3") (pinfunction "3_3") (pintype "passive"))
      (node (ref "VALVE2") (pin "4") (pinfunction "4_4") (pintype "passive"))
    )
    (net (code "103") (name "/REF3") (class "Default")
      (node (ref "R10") (pin "2") (pinfunction "2_2") (pintype "passive"))
      (node (ref "R11") (pin "1") (pinfunction "1_1") (pintype "passive"))
      (node (ref "VALVE3") (pin "3") (pinfunction "3_3") (pintype "passive"))
      (node (ref "VALVE3") (pin "4") (pinfunction "4_4") (pintype "passive"))
    )
    (net (code "104") (name "/REF_1") (class "Default")
      (node (ref "R6") (pin "2") (pinfunction "2_2") (pintype "passive"))
      (node (ref "R7") (pin "1") (pinfunction "1_1") (pintype "passive"))
      (node (ref "VALVE1") (pin "3") (pinfunction "3_3") (pintype "passive"))
      (node (ref "VALVE1") (pin "4") (pinfunction "4_4") (pintype "passive"))
    )
    (net (code "105") (name "/RESET_1280") (class "Default")
      (node (ref "ISP") (pin "3") (pinfunction "P$3_3") (pintype "bidirectional"))
      (node (ref "ISP1") (pin "3") (pinfunction "P$3_3") (pintype "bidirectional"))
      (node (ref "J11") (pin "6") (pinfunction "6_6") (pintype "bidirectional"))
    )
    (net (code "112") (name "/VDD3V3") (class "Default")
      (node (ref "J11") (pin "5") (pinfunction "5_5") (pintype "bidirectional"))
    )
    (net (code "113") (name "/VDD_EXT") (class "Default")
      (node (ref "J11") (pin "1") (pinfunction "1_1") (pintype "bidirectional"))
    )
    (net (code "114") (name "/W_1") (class "Default")
      (node (ref "IC2") (pin "16") (pinfunction "W_16") (pintype "input"))
      (node (ref "VALVE1") (pin "1") (pinfunction "1_1") (pintype "passive"))
      (node (ref "VALVE1") (pin "2") (pinfunction "2_2") (pintype "passive"))
    )
    (net (code "115") (name "/W_2") (class "Default")
      (node (ref "IC3") (pin "16") (pinfunction "W_16") (pintype "input"))
      (node (ref "VALVE2") (pin "1") (pinfunction "1_1") (pintype "passive"))
      (node (ref "VALVE2") (pin "2") (pinfunction "2_2") (pintype "passive"))
    )
    (net (code "116") (name "/W_3") (class "Default")
      (node (ref "IC4") (pin "16") (pinfunction "W_16") (pintype "input"))
      (node (ref "VALVE3") (pin "1") (pinfunction "1_1") (pintype "passive"))
      (node (ref "VALVE3") (pin "2") (pinfunction "2_2") (pintype "passive"))
    )
    (net (code "117") (name "GND") (class "Default")
      (node (ref "5VDC") (pin "1") (pinfunction "1_1") (pintype "passive"))
      (node (ref "5VDC") (pin "3") (pinfunction "3_3") (pintype "passive"))
      (node (ref "5VDC") (pin "5") (pinfunction "5_5") (pintype "passive"))
      (node (ref "8~1") (pin "7") (pinfunction "P$7_7") (pintype "bidirectional"))
      (node (ref "8~13") (pin "7") (pinfunction "P$7_7") (pintype "bidirectional"))
      (node (ref "C1") (pin "2") (pinfunction "2_2") (pintype "passive"))
      (node (ref "C11") (pin "2") (pinfunction "2_2") (pintype "passive"))
      (node (ref "C12") (pin "2") (pinfunction "2_2") (pintype "passive"))
      (node (ref "C13") (pin "2") (pinfunction "2_2") (pintype "passive"))
      (node (ref "C14") (pin "2") (pinfunction "2_2") (pintype "passive"))
      (node (ref "C15") (pin "2") (pinfunction "2_2") (pintype "passive"))
      (node (ref "C16") (pin "2") (pinfunction "2_2") (pintype "passive"))
      (node (ref "C17") (pin "2") (pinfunction "2_2") (pintype "passive"))
      (node (ref "C2") (pin "2") (pinfunction "2_2") (pintype "passive"))
      (node (ref "C3") (pin "2") (pinfunction "2_2") (pintype "passive"))
      (node (ref "C4") (pin "2") (pinfunction "2_2") (pintype "passive"))
      (node (ref "C5") (pin "2") (pinfunction "2_2") (pintype "passive"))
      (node (ref "C9") (pin "2") (pinfunction "2_2") (pintype "passive"))
      (node (ref "ESTOP") (pin "1") (pinfunction "1_1") (pintype "passive"))
      (node (ref "ESTOP") (pin "3") (pinfunction "3_3") (pintype "passive"))
      (node (ref "ESTOP") (pin "5") (pinfunction "5_5") (pintype "passive"))
      (node (ref "GND_J1") (pin "1") (pinfunction "P$1_1") (pintype "bidirectional"))
      (node (ref "GND_J1") (pin "2") (pinfunction "P$2_2") (pintype "bidirectional"))
      (node (ref "GND_J1") (pin "3") (pinfunction "P$3_3") (pintype "bidirectional"))
      (node (ref "GND_J1") (pin "4") (pinfunction "P$4_4") (pintype "bidirectional"))
      (node (ref "GND_J1") (pin "5") (pinfunction "P$5_5") (pintype "bidirectional"))
      (node (ref "GND_J1") (pin "6") (pinfunction "P$6_6") (pintype "bidirectional"))
      (node (ref "GND_J1") (pin "7") (pinfunction "P$7_7") (pintype "bidirectional"))
      (node (ref "GND_J1") (pin "8") (pinfunction "P$8_8") (pintype "bidirectional"))
      (node (ref "GND_J2") (pin "1") (pinfunction "P$1_1") (pintype "bidirectional"))
      (node (ref "GND_J2") (pin "2") (pinfunction "P$2_2") (pintype "bidirectional"))
      (node (ref "GND_J2") (pin "3") (pinfunction "P$3_3") (pintype "bidirectional"))
      (node (ref "GND_J2") (pin "4") (pinfunction "P$4_4") (pintype "bidirectional"))
      (node (ref "GND_J2") (pin "5") (pinfunction "P$5_5") (pintype "bidirectional"))
      (node (ref "GND_J2") (pin "6") (pinfunction "P$6_6") (pintype "bidirectional"))
      (node (ref "GND_J2") (pin "7") (pinfunction "P$7_7") (pintype "bidirectional"))
      (node (ref "GND_J2") (pin "8") (pinfunction "P$8_8") (pintype "bidirectional"))
      (node (ref "I2C") (pin "2") (pinfunction "P$2_2") (pintype "bidirectional"))
      (node (ref "IC1") (pin "2") (pinfunction "GND_2") (pintype "passive"))
      (node (ref "IC2") (pin "4") (pinfunction "GND_4") (pintype "power_in"))
      (node (ref "IC3") (pin "4") (pinfunction "GND_4") (pintype "power_in"))
      (node (ref "IC4") (pin "4") (pinfunction "GND_4") (pintype "power_in"))
      (node (ref "ISP") (pin "4") (pinfunction "P$4_4") (pintype "bidirectional"))
      (node (ref "ISP1") (pin "4") (pinfunction "P$4_4") (pintype "bidirectional"))
      (node (ref "J11") (pin "2") (pinfunction "2_2") (pintype "bidirectional"))
      (node (ref "J11") (pin "3") (pinfunction "3_3") (pintype "bidirectional"))
      (node (ref "JP1") (pin "10") (pinfunction "10_10") (pintype "passive"))
      (node (ref "JP1") (pin "4") (pinfunction "4_4") (pintype "passive"))
      (node (ref "JP1") (pin "6") (pinfunction "6_6") (pintype "passive"))
      (node (ref "JP1") (pin "8") (pinfunction "8_8") (pintype "passive"))
      (node (ref "JP2") (pin "10") (pinfunction "10_10") (pintype "passive"))
      (node (ref "JP2") (pin "4") (pinfunction "4_4") (pintype "passive"))
      (node (ref "JP2") (pin "6") (pinfunction "6_6") (pintype "passive"))
      (node (ref "JP2") (pin "8") (pinfunction "8_8") (pintype "passive"))
      (node (ref "JP4") (pin "10") (pinfunction "10_10") (pintype "passive"))
      (node (ref "JP4") (pin "12") (pinfunction "12_12") (pintype "passive"))
      (node (ref "JP4") (pin "14") (pinfunction "14_14") (pintype "passive"))
      (node (ref "JP4") (pin "16") (pinfunction "16_16") (pintype "passive"))
      (node (ref "JP4") (pin "2") (pinfunction "2_2") (pintype "passive"))
      (node (ref "JP4") (pin "4") (pinfunction "4_4") (pintype "passive"))
      (node (ref "JP4") (pin "6") (pinfunction "6_6") (pintype "passive"))
      (node (ref "JP4") (pin "8") (pinfunction "8_8") (pintype "passive"))
      (node (ref "JP5") (pin "10") (pinfunction "10_10") (pintype "passive"))
      (node (ref "JP5") (pin "4") (pinfunction "4_4") (pintype "passive"))
      (node (ref "JP5") (pin "6") (pinfunction "6_6") (pintype "passive"))
      (node (ref "JP5") (pin "8") (pinfunction "8_8") (pintype "passive"))
      (node (ref "LED1") (pin "C") (pinfunction "C_C") (pintype "passive"))
      (node (ref "LED4") (pin "C") (pinfunction "C_C") (pintype "passive"))
      (node (ref "LED5") (pin "C") (pinfunction "C_C") (pintype "passive"))
      (node (ref "R2") (pin "1") (pinfunction "1_1") (pintype "passive"))
      (node (ref "SPF2") (pin "1") (pinfunction "S_1") (pintype "passive"))
      (node (ref "SPF2") (pin "2") (pinfunction "S1_2") (pintype "passive"))
      (node (ref "SPF3") (pin "1") (pinfunction "S_1") (pintype "passive"))
      (node (ref "SPF3") (pin "2") (pinfunction "S1_2") (pintype "passive"))
      (node (ref "UART1A") (pin "2") (pinfunction "2_2") (pintype "passive"))
      (node (ref "X1") (pin "2") (pinfunction "KL_2") (pintype "passive"))
    )
    (net (code "118") (name "Net-(LED1-PadA)") (class "Default")
      (node (ref "LED1") (pin "A") (pinfunction "A_A") (pintype "passive"))
      (node (ref "R13") (pin "1") (pinfunction "1_1") (pintype "passive"))
    )
    (net (code "119") (name "Net-(LED2-PadA)") (class "Default")
      (node (ref "LED2") (pin "A") (pinfunction "A_A") (pintype "passive"))
      (node (ref "LED3") (pin "C") (pinfunction "C_C") (pintype "passive"))
      (node (ref "R12") (pin "1") (pinfunction "1_1") (pintype "passive"))
    )
    (net (code "120") (name "Net-(LED4-PadA)") (class "Default")
      (node (ref "LED4") (pin "A") (pinfunction "A_A") (pintype "passive"))
      (node (ref "R14") (pin "1") (pinfunction "1_1") (pintype "passive"))
    )
    (net (code "121") (name "Net-(LED5-PadA)") (class "Default")
      (node (ref "LED5") (pin "A") (pinfunction "A_A") (pintype "passive"))
      (node (ref "R1") (pin "1") (pinfunction "1_1") (pintype "passive"))
    )
    (net (code "122") (name "unconnected-(ADDR-Pad2)") (class "Default")
      (node (ref "ADDR") (pin "2") (pinfunction "2_2") (pintype "passive"))
    )
    (net (code "123") (name "unconnected-(ADDR-Pad4)") (class "Default")
      (node (ref "ADDR") (pin "4") (pinfunction "4_4") (pintype "passive"))
    )
    (net (code "124") (name "unconnected-(ADDR-Pad6)") (class "Default")
      (node (ref "ADDR") (pin "6") (pinfunction "6_6") (pintype "passive"))
    )
    (net (code "125") (name "unconnected-(ADDR-Pad8)") (class "Default")
      (node (ref "ADDR") (pin "8") (pinfunction "8_8") (pintype "passive"))
    )
    (net (code "126") (name "unconnected-(IC2-NC1-Pad8)") (class "Default")
      (node (ref "IC2") (pin "8") (pinfunction "NC1_8") (pintype "no_connect"))
    )
    (net (code "127") (name "unconnected-(IC2-NC2-Pad9)") (class "Default")
      (node (ref "IC2") (pin "9") (pinfunction "NC2_9") (pintype "no_connect"))
    )
    (net (code "128") (name "unconnected-(IC2-NC3-Pad10)") (class "Default")
      (node (ref "IC2") (pin "10") (pinfunction "NC3_10") (pintype "no_connect"))
    )
    (net (code "129") (name "unconnected-(IC2-NC4-Pad15)") (class "Default")
      (node (ref "IC2") (pin "15") (pinfunction "NC4_15") (pintype "no_connect"))
    )
    (net (code "130") (name "unconnected-(IC2-SDO-Pad13)") (class "Default")
      (node (ref "IC2") (pin "13") (pinfunction "SDO_13") (pintype "output"))
    )
    (net (code "131") (name "unconnected-(IC3-NC1-Pad8)") (class "Default")
      (node (ref "IC3") (pin "8") (pinfunction "NC1_8") (pintype "no_connect"))
    )
    (net (code "132") (name "unconnected-(IC3-NC2-Pad9)") (class "Default")
      (node (ref "IC3") (pin "9") (pinfunction "NC2_9") (pintype "no_connect"))
    )
    (net (code "133") (name "unconnected-(IC3-NC3-Pad10)") (class "Default")
      (node (ref "IC3") (pin "10") (pinfunction "NC3_10") (pintype "no_connect"))
    )
    (net (code "134") (name "unconnected-(IC3-NC4-Pad15)") (class "Default")
      (node (ref "IC3") (pin "15") (pinfunction "NC4_15") (pintype "no_connect"))
    )
    (net (code "135") (name "unconnected-(IC3-SDO-Pad13)") (class "Default")
      (node (ref "IC3") (pin "13") (pinfunction "SDO_13") (pintype "output"))
    )
    (net (code "136") (name "unconnected-(IC4-NC1-Pad8)") (class "Default")
      (node (ref "IC4") (pin "8") (pinfunction "NC1_8") (pintype "no_connect"))
    )
    (net (code "137") (name "unconnected-(IC4-NC2-Pad9)") (class "Default")
      (node (ref "IC4") (pin "9") (pinfunction "NC2_9") (pintype "no_connect"))
    )
    (net (code "138") (name "unconnected-(IC4-NC3-Pad10)") (class "Default")
      (node (ref "IC4") (pin "10") (pinfunction "NC3_10") (pintype "no_connect"))
    )
    (net (code "139") (name "unconnected-(IC4-NC4-Pad15)") (class "Default")
      (node (ref "IC4") (pin "15") (pinfunction "NC4_15") (pintype "no_connect"))
    )
    (net (code "140") (name "unconnected-(IC4-SDO-Pad13)") (class "Default")
      (node (ref "IC4") (pin "13") (pinfunction "SDO_13") (pintype "output"))
    )
  )
)
